# micromouse.net
KiCad netlist of a schematic drawn in EAGLE
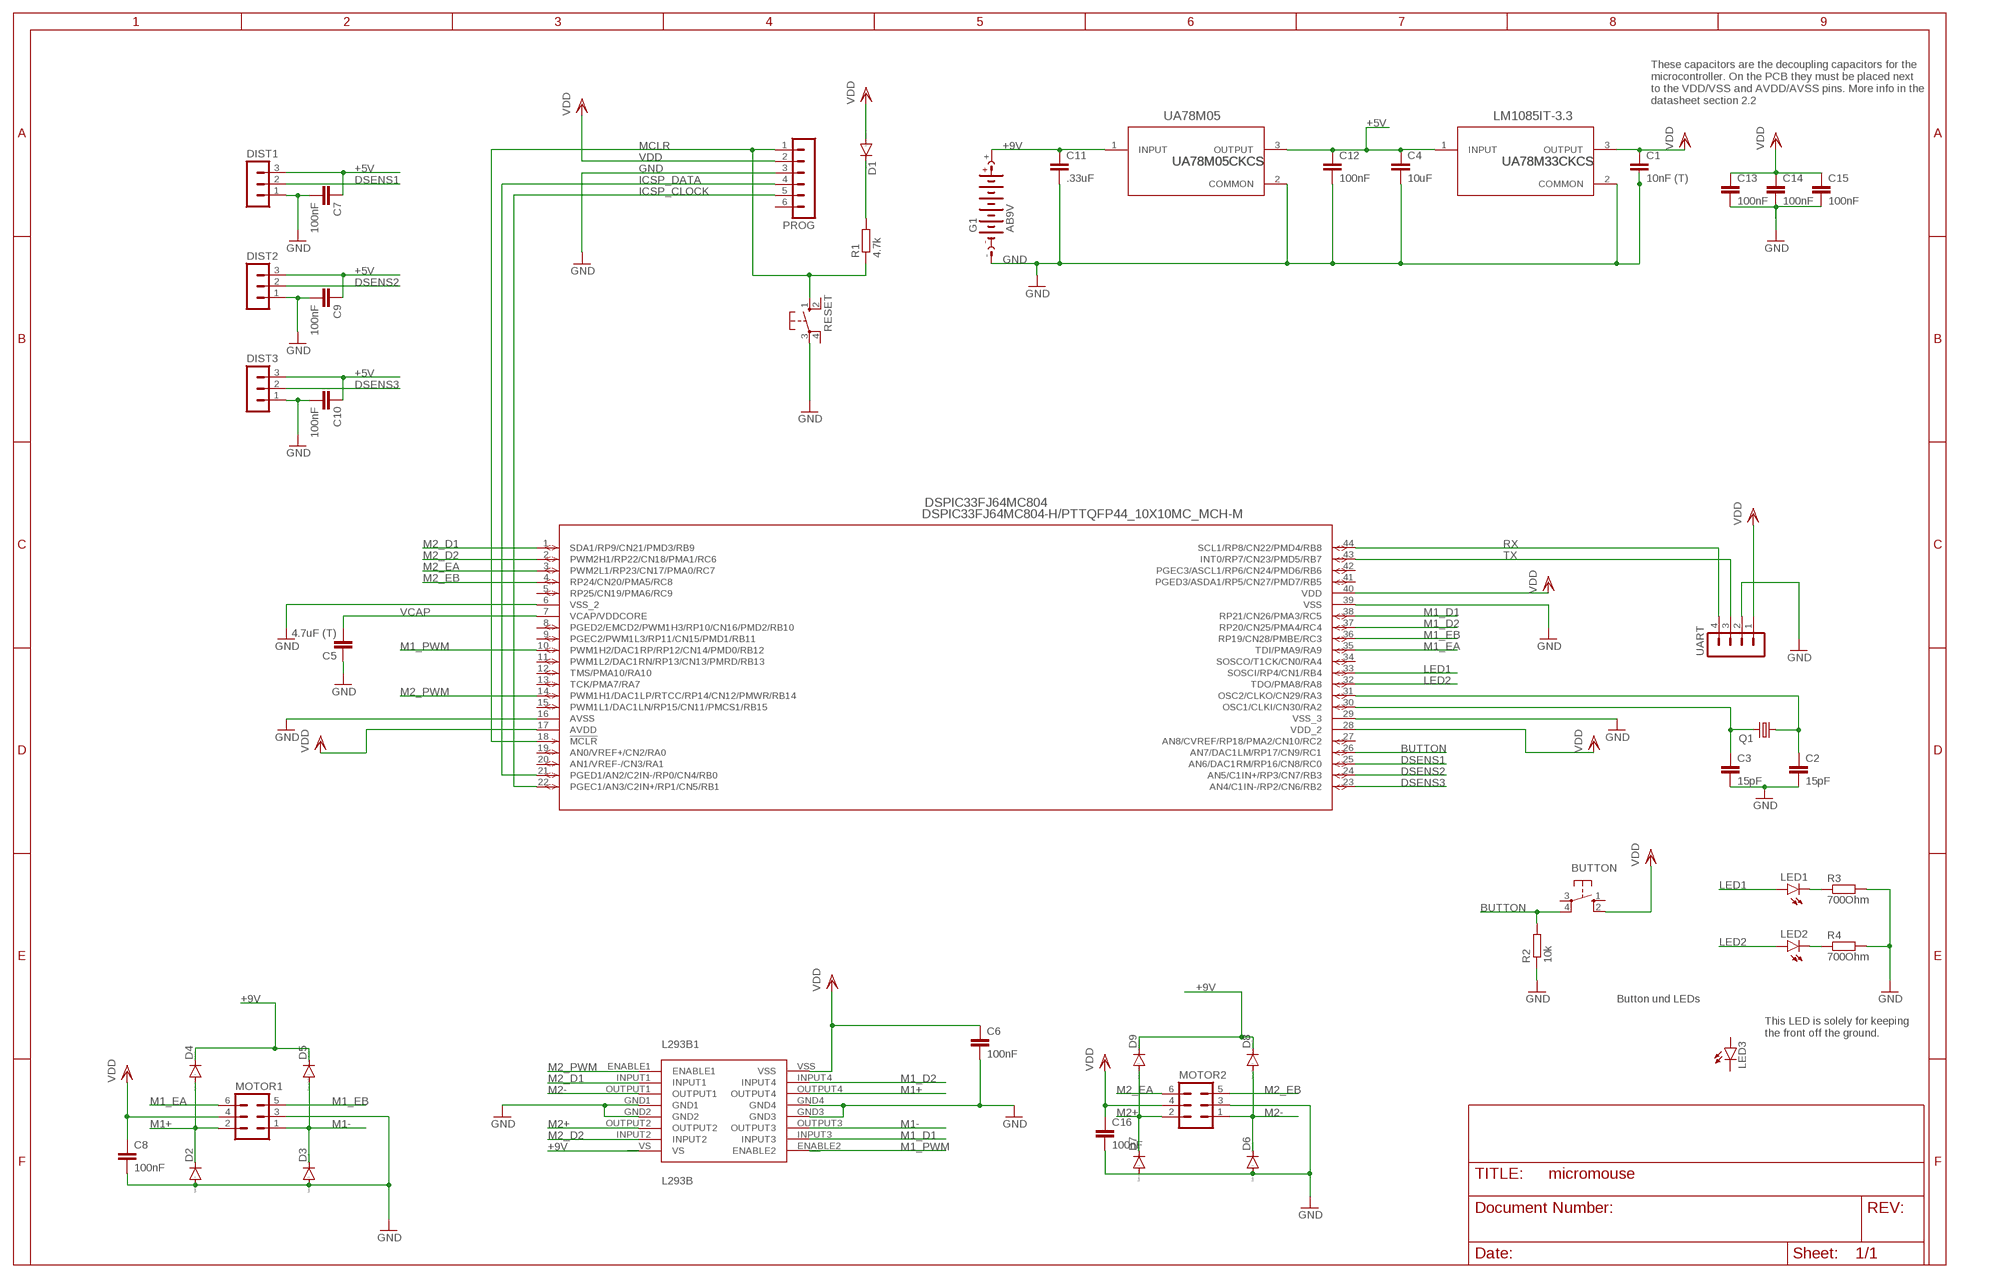
[diagram p0: schematic, sheet 1]

(export (version "E")
  (design (tool "Eeschema 10.0.6"))
  (components
    (comp (ref "BUTTON")
      (value "10-XX")
      (footprint "eagle-import:B3F-10XX")
      (fields (field (name "MPN") "B3F-1000"))
      (libsource (lib "eagle-import") (part "10-XX"))
    )
    (comp (ref "C1")
      (value "10nF (T)")
      (footprint "eagle-import:C0805")
      (libsource (lib "eagle-import") (part "C-EUC0805"))
    )
    (comp (ref "C2")
      (value "15pF")
      (footprint "eagle-import:C0805")
      (libsource (lib "eagle-import") (part "C-EUC0805"))
    )
    (comp (ref "C3")
      (value "15pF")
      (footprint "eagle-import:C0805")
      (libsource (lib "eagle-import") (part "C-EUC0805"))
    )
    (comp (ref "C4")
      (value "10uF")
      (footprint "eagle-import:C0805")
      (libsource (lib "eagle-import") (part "C-EUC0805"))
    )
    (comp (ref "C5")
      (value "4.7uF (T)")
      (footprint "eagle-import:C0805")
      (libsource (lib "eagle-import") (part "C-EUC0805"))
    )
    (comp (ref "C6")
      (value "100nF")
      (footprint "eagle-import:C0805")
      (libsource (lib "eagle-import") (part "C-EUC0805"))
    )
    (comp (ref "C7")
      (value "100nF")
      (footprint "eagle-import:C0805")
      (libsource (lib "eagle-import") (part "C-EUC0805"))
    )
    (comp (ref "C8")
      (value "100nF")
      (footprint "eagle-import:C0805")
      (libsource (lib "eagle-import") (part "C-EUC0805"))
    )
    (comp (ref "C9")
      (value "100nF")
      (footprint "eagle-import:C0805")
      (libsource (lib "eagle-import") (part "C-EUC0805"))
    )
    (comp (ref "C10")
      (value "100nF")
      (footprint "eagle-import:C0805")
      (libsource (lib "eagle-import") (part "C-EUC0805"))
    )
    (comp (ref "C11")
      (value ".33uF")
      (footprint "eagle-import:C0805")
      (libsource (lib "eagle-import") (part "C-EUC0805"))
    )
    (comp (ref "C12")
      (value "100nF")
      (footprint "eagle-import:C0805")
      (libsource (lib "eagle-import") (part "C-EUC0805"))
    )
    (comp (ref "C13")
      (value "100nF")
      (footprint "eagle-import:C0805")
      (libsource (lib "eagle-import") (part "C-EUC0805"))
    )
    (comp (ref "C14")
      (value "100nF")
      (footprint "eagle-import:C0805")
      (libsource (lib "eagle-import") (part "C-EUC0805"))
    )
    (comp (ref "C15")
      (value "100nF")
      (footprint "eagle-import:C0805")
      (libsource (lib "eagle-import") (part "C-EUC0805"))
    )
    (comp (ref "C16")
      (value "100nF")
      (footprint "eagle-import:C0805")
      (libsource (lib "eagle-import") (part "C-EUC0805"))
    )
    (comp (ref "D1")
      (value "DIODE-SOD123")
      (footprint "eagle-import:SOD123")
      (libsource (lib "eagle-import") (part "DIODE-SOD123"))
    )
    (comp (ref "D2")
      (value "DIODE-SOD123")
      (footprint "eagle-import:SOD123")
      (libsource (lib "eagle-import") (part "DIODE-SOD123"))
    )
    (comp (ref "D3")
      (value "DIODE-SOD123")
      (footprint "eagle-import:SOD123")
      (libsource (lib "eagle-import") (part "DIODE-SOD123"))
    )
    (comp (ref "D4")
      (value "DIODE-SOD123")
      (footprint "eagle-import:SOD123")
      (libsource (lib "eagle-import") (part "DIODE-SOD123"))
    )
    (comp (ref "D5")
      (value "DIODE-SOD123")
      (footprint "eagle-import:SOD123")
      (libsource (lib "eagle-import") (part "DIODE-SOD123"))
    )
    (comp (ref "D6")
      (value "DIODE-SOD123")
      (footprint "eagle-import:SOD123")
      (libsource (lib "eagle-import") (part "DIODE-SOD123"))
    )
    (comp (ref "D7")
      (value "DIODE-SOD123")
      (footprint "eagle-import:SOD123")
      (libsource (lib "eagle-import") (part "DIODE-SOD123"))
    )
    (comp (ref "D8")
      (value "DIODE-SOD123")
      (footprint "eagle-import:SOD123")
      (libsource (lib "eagle-import") (part "DIODE-SOD123"))
    )
    (comp (ref "D9")
      (value "DIODE-SOD123")
      (footprint "eagle-import:SOD123")
      (libsource (lib "eagle-import") (part "DIODE-SOD123"))
    )
    (comp (ref "DIST1")
      (value "MA03-1")
      (footprint "eagle-import:MA03-1")
      (libsource (lib "eagle-import") (part "MA03-1"))
    )
    (comp (ref "DIST2")
      (value "MA03-1")
      (footprint "eagle-import:MA03-1")
      (libsource (lib "eagle-import") (part "MA03-1"))
    )
    (comp (ref "DIST3")
      (value "MA03-1")
      (footprint "eagle-import:MA03-1")
      (libsource (lib "eagle-import") (part "MA03-1"))
    )
    (comp (ref "DSPIC33FJ64MC804")
      (value "DSPIC33FJ64MC804-H/PTTQFP44_10X10MC_MCH-M")
      (footprint "eagle-import:TQFP44_10X10MC_MCH-M")
      (fields
        (field (name "MANUFACTURER_PART_NUMBER") "DSPIC33FJ64MC804-H/PT")
        (field (name "COPYRIGHT") "Copyright (C) 2022 Ultra Librarian. All rights reserved.")
      )
      (libsource (lib "eagle-import") (part "DSPIC33FJ64MC804-H/PTTQFP44_10X10MC_MCH-M"))
    )
    (comp (ref "G1")
      (value "AB9V")
      (footprint "eagle-import:AB9V")
      (libsource (lib "eagle-import") (part "AB9V"))
    )
    (comp (ref "L293B1")
      (value "L293B")
      (footprint "eagle-import:L293P-DIP16")
      (libsource (lib "eagle-import") (part "L293B"))
    )
    (comp (ref "LED1")
      (value "LEDCHIP-LED0805")
      (footprint "eagle-import:CHIP-LED0805")
      (libsource (lib "eagle-import") (part "LEDCHIP-LED0805"))
    )
    (comp (ref "LED2")
      (value "LEDCHIP-LED0805")
      (footprint "eagle-import:CHIP-LED0805")
      (libsource (lib "eagle-import") (part "LEDCHIP-LED0805"))
    )
    (comp (ref "LED3")
      (value "LED5MM")
      (footprint "eagle-import:LED5MM")
      (libsource (lib "eagle-import") (part "LED5MM"))
    )
    (comp (ref "LM1085IT-3.3")
      (value "UA78M33CKCS")
      (footprint "eagle-import:KCS0003B")
      (fields
        (field (name "MANUFACTURER_PART_NUMBER") "UA78M05CKCS")
        (field (name "COPYRIGHT") "Copyright (C) 2022 Ultra Librarian. All rights reserved.")
      )
      (libsource (lib "eagle-import") (part "UA78M33CKCS"))
    )
    (comp (ref "MOTOR1")
      (value "MA03-2")
      (footprint "eagle-import:MA03-2")
      (libsource (lib "eagle-import") (part "MA03-2"))
    )
    (comp (ref "MOTOR2")
      (value "MA03-2")
      (footprint "eagle-import:MA03-2")
      (libsource (lib "eagle-import") (part "MA03-2"))
    )
    (comp (ref "PROG")
      (value "MA06-1")
      (footprint "eagle-import:MA06-1")
      (libsource (lib "eagle-import") (part "MA06-1"))
    )
    (comp (ref "Q1")
      (value "CRYSTALHC49S")
      (footprint "eagle-import:HC49_S")
      (libsource (lib "eagle-import") (part "CRYSTALHC49S"))
    )
    (comp (ref "R1")
      (value "4.7k")
      (footprint "eagle-import:R0805")
      (libsource (lib "eagle-import") (part "R-EU_R0805"))
    )
    (comp (ref "R2")
      (value "10k")
      (footprint "eagle-import:R0805")
      (libsource (lib "eagle-import") (part "R-EU_R0805"))
    )
    (comp (ref "R3")
      (value "700Ohm")
      (footprint "eagle-import:R0805")
      (libsource (lib "eagle-import") (part "R-EU_R0805"))
    )
    (comp (ref "R4")
      (value "700Ohm")
      (footprint "eagle-import:R0805")
      (libsource (lib "eagle-import") (part "R-EU_R0805"))
    )
    (comp (ref "RESET")
      (value "10-XX")
      (footprint "eagle-import:B3F-10XX")
      (fields (field (name "MPN") "B3F-1000"))
      (libsource (lib "eagle-import") (part "10-XX"))
    )
    (comp (ref "UA78M05")
      (value "UA78M05CKCS")
      (footprint "eagle-import:KCS0003B")
      (fields (field (name "COPYRIGHT") "Copyright (C) 2022 Ultra Librarian. All rights reserved."))
      (libsource (lib "eagle-import") (part "UA78M05CKCS"))
    )
    (comp (ref "UART")
      (value "MA04-1")
      (footprint "eagle-import:MA04-1")
      (libsource (lib "eagle-import") (part "MA04-1"))
    )
  )
  (nets
    (net (code "1") (name "/+5V") (class "Default")
      (node (ref "C10") (pin "1") (pinfunction "1_1") (pintype "passive"))
      (node (ref "C12") (pin "1") (pinfunction "1_1") (pintype "passive"))
      (node (ref "C4") (pin "1") (pinfunction "1_1") (pintype "passive"))
      (node (ref "C7") (pin "1") (pinfunction "1_1") (pintype "passive"))
      (node (ref "C9") (pin "1") (pinfunction "1_1") (pintype "passive"))
      (node (ref "DIST1") (pin "3") (pinfunction "3_3") (pintype "passive"))
      (node (ref "DIST2") (pin "3") (pinfunction "3_3") (pintype "passive"))
      (node (ref "DIST3") (pin "3") (pinfunction "3_3") (pintype "passive"))
      (node (ref "LM1085IT-3.3") (pin "1") (pinfunction "INPUT_1") (pintype "power_in"))
      (node (ref "UA78M05") (pin "3") (pinfunction "OUTPUT_3") (pintype "power_in"))
    )
    (net (code "2") (name "/+9V") (class "Default")
      (node (ref "C11") (pin "1") (pinfunction "1_1") (pintype "passive"))
      (node (ref "D4") (pin "C") (pinfunction "C_C") (pintype "passive"))
      (node (ref "D5") (pin "C") (pinfunction "C_C") (pintype "passive"))
      (node (ref "D8") (pin "C") (pinfunction "C_C") (pintype "passive"))
      (node (ref "D9") (pin "C") (pinfunction "C_C") (pintype "passive"))
      (node (ref "G1") (pin "+") (pinfunction "+_+") (pintype "passive"))
      (node (ref "L293B1") (pin "VS") (pinfunction "VS_VS") (pintype "bidirectional"))
      (node (ref "UA78M05") (pin "1") (pinfunction "INPUT_1") (pintype "power_in"))
    )
    (net (code "3") (name "/BUTTON") (class "Default")
      (node (ref "BUTTON") (pin "4") (pinfunction "P1_4") (pintype "passive"))
      (node (ref "DSPIC33FJ64MC804") (pin "26") (pinfunction "AN7/DAC1LM/RP17/CN9/RC1_26") (pintype "bidirectional"))
      (node (ref "R2") (pin "2") (pinfunction "2_2") (pintype "passive"))
    )
    (net (code "4") (name "/DSENS1") (class "Default")
      (node (ref "DIST1") (pin "2") (pinfunction "2_2") (pintype "passive"))
      (node (ref "DSPIC33FJ64MC804") (pin "25") (pinfunction "AN6/DAC1RM/RP16/CN8/RC0_25") (pintype "bidirectional"))
    )
    (net (code "5") (name "/DSENS2") (class "Default")
      (node (ref "DIST2") (pin "2") (pinfunction "2_2") (pintype "passive"))
      (node (ref "DSPIC33FJ64MC804") (pin "24") (pinfunction "AN5/C1IN+/RP3/CN7/RB3_24") (pintype "bidirectional"))
    )
    (net (code "6") (name "/DSENS3") (class "Default")
      (node (ref "DIST3") (pin "2") (pinfunction "2_2") (pintype "passive"))
      (node (ref "DSPIC33FJ64MC804") (pin "23") (pinfunction "AN4/C1IN-/RP2/CN6/RB2_23") (pintype "bidirectional"))
    )
    (net (code "7") (name "/ICSP_CLOCK") (class "Default")
      (node (ref "DSPIC33FJ64MC804") (pin "22") (pinfunction "PGEC1/AN3/C2IN+/RP1/CN5/RB1_22") (pintype "bidirectional"))
      (node (ref "PROG") (pin "5") (pinfunction "5_5") (pintype "passive"))
    )
    (net (code "8") (name "/ICSP_DATA") (class "Default")
      (node (ref "DSPIC33FJ64MC804") (pin "21") (pinfunction "PGED1/AN2/C2IN-/RP0/CN4/RB0_21") (pintype "bidirectional"))
      (node (ref "PROG") (pin "4") (pinfunction "4_4") (pintype "passive"))
    )
    (net (code "9") (name "/LED1") (class "Default")
      (node (ref "DSPIC33FJ64MC804") (pin "33") (pinfunction "SOSCI/RP4/CN1/RB4_33") (pintype "bidirectional"))
      (node (ref "LED1") (pin "A") (pinfunction "A_A") (pintype "passive"))
    )
    (net (code "10") (name "/LED2") (class "Default")
      (node (ref "DSPIC33FJ64MC804") (pin "32") (pinfunction "TDO/PMA8/RA8_32") (pintype "bidirectional"))
      (node (ref "LED2") (pin "A") (pinfunction "A_A") (pintype "passive"))
    )
    (net (code "11") (name "/M1+") (class "Default")
      (node (ref "D2") (pin "C") (pinfunction "C_C") (pintype "passive"))
      (node (ref "D4") (pin "A") (pinfunction "A_A") (pintype "passive"))
      (node (ref "L293B1") (pin "OUTPUT4") (pinfunction "OUTPUT4_OUTPUT4") (pintype "bidirectional"))
      (node (ref "MOTOR1") (pin "2") (pinfunction "2_2") (pintype "passive"))
    )
    (net (code "12") (name "/M1-") (class "Default")
      (node (ref "D3") (pin "C") (pinfunction "C_C") (pintype "passive"))
      (node (ref "D5") (pin "A") (pinfunction "A_A") (pintype "passive"))
      (node (ref "L293B1") (pin "OUTPUT3") (pinfunction "OUTPUT3_OUTPUT3") (pintype "bidirectional"))
      (node (ref "MOTOR1") (pin "1") (pinfunction "1_1") (pintype "passive"))
    )
    (net (code "13") (name "/M1_D1") (class "Default")
      (node (ref "DSPIC33FJ64MC804") (pin "38") (pinfunction "RP21/CN26/PMA3/RC5_38") (pintype "bidirectional"))
      (node (ref "L293B1") (pin "INPUT3") (pinfunction "INPUT3_INPUT3") (pintype "bidirectional"))
    )
    (net (code "14") (name "/M1_D2") (class "Default")
      (node (ref "DSPIC33FJ64MC804") (pin "37") (pinfunction "RP20/CN25/PMA4/RC4_37") (pintype "bidirectional"))
      (node (ref "L293B1") (pin "INPUT4") (pinfunction "INPUT4_INPUT4") (pintype "bidirectional"))
    )
    (net (code "15") (name "/M1_EA") (class "Default")
      (node (ref "DSPIC33FJ64MC804") (pin "35") (pinfunction "TDI/PMA9/RA9_35") (pintype "bidirectional"))
      (node (ref "MOTOR1") (pin "6") (pinfunction "6_6") (pintype "passive"))
    )
    (net (code "16") (name "/M1_EB") (class "Default")
      (node (ref "DSPIC33FJ64MC804") (pin "36") (pinfunction "RP19/CN28/PMBE/RC3_36") (pintype "bidirectional"))
      (node (ref "MOTOR1") (pin "5") (pinfunction "5_5") (pintype "passive"))
    )
    (net (code "17") (name "/M1_PWM") (class "Default")
      (node (ref "DSPIC33FJ64MC804") (pin "10") (pinfunction "PWM1H2/DAC1RP/RP12/CN14/PMD0/RB12_10") (pintype "bidirectional"))
      (node (ref "L293B1") (pin "ENABLE2") (pinfunction "ENABLE2_ENABLE2") (pintype "bidirectional"))
    )
    (net (code "18") (name "/M2+") (class "Default")
      (node (ref "D7") (pin "C") (pinfunction "C_C") (pintype "passive"))
      (node (ref "D9") (pin "A") (pinfunction "A_A") (pintype "passive"))
      (node (ref "L293B1") (pin "OUTPUT2") (pinfunction "OUTPUT2_OUTPUT2") (pintype "bidirectional"))
      (node (ref "MOTOR2") (pin "2") (pinfunction "2_2") (pintype "passive"))
    )
    (net (code "19") (name "/M2-") (class "Default")
      (node (ref "D6") (pin "C") (pinfunction "C_C") (pintype "passive"))
      (node (ref "D8") (pin "A") (pinfunction "A_A") (pintype "passive"))
      (node (ref "L293B1") (pin "OUTPUT1") (pinfunction "OUTPUT1_OUTPUT1") (pintype "bidirectional"))
      (node (ref "MOTOR2") (pin "1") (pinfunction "1_1") (pintype "passive"))
    )
    (net (code "20") (name "/M2_D1") (class "Default")
      (node (ref "DSPIC33FJ64MC804") (pin "1") (pinfunction "SDA1/RP9/CN21/PMD3/RB9_1") (pintype "bidirectional"))
      (node (ref "L293B1") (pin "INPUT1") (pinfunction "INPUT1_INPUT1") (pintype "bidirectional"))
    )
    (net (code "21") (name "/M2_D2") (class "Default")
      (node (ref "DSPIC33FJ64MC804") (pin "2") (pinfunction "PWM2H1/RP22/CN18/PMA1/RC6_2") (pintype "bidirectional"))
      (node (ref "L293B1") (pin "INPUT2") (pinfunction "INPUT2_INPUT2") (pintype "bidirectional"))
    )
    (net (code "22") (name "/M2_EA") (class "Default")
      (node (ref "DSPIC33FJ64MC804") (pin "3") (pinfunction "PWM2L1/RP23/CN17/PMA0/RC7_3") (pintype "bidirectional"))
      (node (ref "MOTOR2") (pin "6") (pinfunction "6_6") (pintype "passive"))
    )
    (net (code "23") (name "/M2_EB") (class "Default")
      (node (ref "DSPIC33FJ64MC804") (pin "4") (pinfunction "RP24/CN20/PMA5/RC8_4") (pintype "bidirectional"))
      (node (ref "MOTOR2") (pin "5") (pinfunction "5_5") (pintype "passive"))
    )
    (net (code "24") (name "/M2_PWM") (class "Default")
      (node (ref "DSPIC33FJ64MC804") (pin "14") (pinfunction "PWM1H1/DAC1LP/RTCC/RP14/CN12/PMWR/RB14_14") (pintype "bidirectional"))
      (node (ref "L293B1") (pin "ENABLE1") (pinfunction "ENABLE1_ENABLE1") (pintype "bidirectional"))
    )
    (net (code "25") (name "/MCLR") (class "Default")
      (node (ref "DSPIC33FJ64MC804") (pin "18") (pinfunction "~{MCLR}_18") (pintype "input"))
      (node (ref "PROG") (pin "1") (pinfunction "1_1") (pintype "passive"))
      (node (ref "R1") (pin "1") (pinfunction "1_1") (pintype "passive"))
      (node (ref "RESET") (pin "1") (pinfunction "S_1") (pintype "passive"))
    )
    (net (code "26") (name "/RX") (class "Default")
      (node (ref "DSPIC33FJ64MC804") (pin "44") (pinfunction "SCL1/RP8/CN22/PMD4/RB8_44") (pintype "bidirectional"))
      (node (ref "UART") (pin "4") (pinfunction "4_4") (pintype "passive"))
    )
    (net (code "27") (name "/TX") (class "Default")
      (node (ref "DSPIC33FJ64MC804") (pin "43") (pinfunction "INT0/RP7/CN23/PMD5/RB7_43") (pintype "bidirectional"))
      (node (ref "UART") (pin "3") (pinfunction "3_3") (pintype "passive"))
    )
    (net (code "28") (name "/VCAP") (class "Default")
      (node (ref "C5") (pin "2") (pinfunction "2_2") (pintype "passive"))
      (node (ref "DSPIC33FJ64MC804") (pin "7") (pinfunction "VCAP/VDDCORE_7") (pintype "power_in"))
    )
    (net (code "29") (name "GND") (class "Default")
      (node (ref "C1") (pin "2") (pinfunction "2_2") (pintype "passive"))
      (node (ref "C10") (pin "2") (pinfunction "2_2") (pintype "passive"))
      (node (ref "C11") (pin "2") (pinfunction "2_2") (pintype "passive"))
      (node (ref "C12") (pin "2") (pinfunction "2_2") (pintype "passive"))
      (node (ref "C13") (pin "2") (pinfunction "2_2") (pintype "passive"))
      (node (ref "C14") (pin "2") (pinfunction "2_2") (pintype "passive"))
      (node (ref "C15") (pin "2") (pinfunction "2_2") (pintype "passive"))
      (node (ref "C16") (pin "2") (pinfunction "2_2") (pintype "passive"))
      (node (ref "C2") (pin "2") (pinfunction "2_2") (pintype "passive"))
      (node (ref "C3") (pin "2") (pinfunction "2_2") (pintype "passive"))
      (node (ref "C4") (pin "2") (pinfunction "2_2") (pintype "passive"))
      (node (ref "C5") (pin "1") (pinfunction "1_1") (pintype "passive"))
      (node (ref "C6") (pin "2") (pinfunction "2_2") (pintype "passive"))
      (node (ref "C7") (pin "2") (pinfunction "2_2") (pintype "passive"))
      (node (ref "C8") (pin "2") (pinfunction "2_2") (pintype "passive"))
      (node (ref "C9") (pin "2") (pinfunction "2_2") (pintype "passive"))
      (node (ref "D2") (pin "A") (pinfunction "A_A") (pintype "passive"))
      (node (ref "D3") (pin "A") (pinfunction "A_A") (pintype "passive"))
      (node (ref "D6") (pin "A") (pinfunction "A_A") (pintype "passive"))
      (node (ref "D7") (pin "A") (pinfunction "A_A") (pintype "passive"))
      (node (ref "DIST1") (pin "1") (pinfunction "1_1") (pintype "passive"))
      (node (ref "DIST2") (pin "1") (pinfunction "1_1") (pintype "passive"))
      (node (ref "DIST3") (pin "1") (pinfunction "1_1") (pintype "passive"))
      (node (ref "DSPIC33FJ64MC804") (pin "16") (pinfunction "AVSS_16") (pintype "power_in"))
      (node (ref "DSPIC33FJ64MC804") (pin "29") (pinfunction "VSS_3_29") (pintype "power_in"))
      (node (ref "DSPIC33FJ64MC804") (pin "39") (pinfunction "VSS_39") (pintype "power_in"))
      (node (ref "DSPIC33FJ64MC804") (pin "6") (pinfunction "VSS_2_6") (pintype "power_in"))
      (node (ref "G1") (pin "-") (pinfunction "-_-") (pintype "passive"))
      (node (ref "L293B1") (pin "GND1") (pinfunction "GND1_GND1") (pintype "bidirectional"))
      (node (ref "L293B1") (pin "GND2") (pinfunction "GND2_GND2") (pintype "bidirectional"))
      (node (ref "L293B1") (pin "GND3") (pinfunction "GND3_GND3") (pintype "bidirectional"))
      (node (ref "L293B1") (pin "GND4") (pinfunction "GND4_GND4") (pintype "bidirectional"))
      (node (ref "LM1085IT-3.3") (pin "2") (pinfunction "COMMON_2") (pintype "power_in"))
      (node (ref "MOTOR1") (pin "3") (pinfunction "3_3") (pintype "passive"))
      (node (ref "MOTOR2") (pin "3") (pinfunction "3_3") (pintype "passive"))
      (node (ref "PROG") (pin "3") (pinfunction "3_3") (pintype "passive"))
      (node (ref "R2") (pin "1") (pinfunction "1_1") (pintype "passive"))
      (node (ref "R3") (pin "2") (pinfunction "2_2") (pintype "passive"))
      (node (ref "R4") (pin "2") (pinfunction "2_2") (pintype "passive"))
      (node (ref "RESET") (pin "3") (pinfunction "P_3") (pintype "passive"))
      (node (ref "UA78M05") (pin "2") (pinfunction "COMMON_2") (pintype "power_in"))
      (node (ref "UART") (pin "2") (pinfunction "2_2") (pintype "passive"))
    )
    (net (code "30") (name "Net-(D1-PadC)") (class "Default")
      (node (ref "D1") (pin "C") (pinfunction "C_C") (pintype "passive"))
      (node (ref "R1") (pin "2") (pinfunction "2_2") (pintype "passive"))
    )
    (net (code "31") (name "Net-(DSPIC33FJ64MC804-OSC1{slash}CLKI{slash}CN30{slash}RA2)") (class "Default")
      (node (ref "C3") (pin "1") (pinfunction "1_1") (pintype "passive"))
      (node (ref "DSPIC33FJ64MC804") (pin "30") (pinfunction "OSC1/CLKI/CN30/RA2_30") (pintype "bidirectional"))
      (node (ref "Q1") (pin "2") (pinfunction "2_2") (pintype "passive"))
    )
    (net (code "32") (name "Net-(DSPIC33FJ64MC804-OSC2{slash}CLKO{slash}CN29{slash}RA3)") (class "Default")
      (node (ref "C2") (pin "1") (pinfunction "1_1") (pintype "passive"))
      (node (ref "DSPIC33FJ64MC804") (pin "31") (pinfunction "OSC2/CLKO/CN29/RA3_31") (pintype "bidirectional"))
      (node (ref "Q1") (pin "1") (pinfunction "1_1") (pintype "passive"))
    )
    (net (code "33") (name "Net-(LED1-PadC)") (class "Default")
      (node (ref "LED1") (pin "C") (pinfunction "C_C") (pintype "passive"))
      (node (ref "R3") (pin "1") (pinfunction "1_1") (pintype "passive"))
    )
    (net (code "34") (name "Net-(LED2-PadC)") (class "Default")
      (node (ref "LED2") (pin "C") (pinfunction "C_C") (pintype "passive"))
      (node (ref "R4") (pin "1") (pinfunction "1_1") (pintype "passive"))
    )
    (net (code "35") (name "VDD") (class "Default")
      (node (ref "BUTTON") (pin "2") (pinfunction "S1_2") (pintype "passive"))
      (node (ref "C1") (pin "1") (pinfunction "1_1") (pintype "passive"))
      (node (ref "C13") (pin "1") (pinfunction "1_1") (pintype "passive"))
      (node (ref "C14") (pin "1") (pinfunction "1_1") (pintype "passive"))
      (node (ref "C15") (pin "1") (pinfunction "1_1") (pintype "passive"))
      (node (ref "C16") (pin "1") (pinfunction "1_1") (pintype "passive"))
      (node (ref "C6") (pin "1") (pinfunction "1_1") (pintype "passive"))
      (node (ref "C8") (pin "1") (pinfunction "1_1") (pintype "passive"))
      (node (ref "D1") (pin "A") (pinfunction "A_A") (pintype "passive"))
      (node (ref "DSPIC33FJ64MC804") (pin "17") (pinfunction "AVDD_17") (pintype "power_in"))
      (node (ref "DSPIC33FJ64MC804") (pin "28") (pinfunction "VDD_2_28") (pintype "power_in"))
      (node (ref "DSPIC33FJ64MC804") (pin "40") (pinfunction "VDD_40") (pintype "power_in"))
      (node (ref "L293B1") (pin "VSS") (pinfunction "VSS_VSS") (pintype "bidirectional"))
      (node (ref "LM1085IT-3.3") (pin "3") (pinfunction "OUTPUT_3") (pintype "power_in"))
      (node (ref "MOTOR1") (pin "4") (pinfunction "4_4") (pintype "passive"))
      (node (ref "MOTOR2") (pin "4") (pinfunction "4_4") (pintype "passive"))
      (node (ref "PROG") (pin "2") (pinfunction "2_2") (pintype "passive"))
      (node (ref "UART") (pin "1") (pinfunction "1_1") (pintype "passive"))
    )
    (net (code "36") (name "unconnected-(BUTTON-P-Pad3)") (class "Default")
      (node (ref "BUTTON") (pin "3") (pinfunction "P_3") (pintype "passive"))
    )
    (net (code "37") (name "unconnected-(BUTTON-S-Pad1)") (class "Default")
      (node (ref "BUTTON") (pin "1") (pinfunction "S_1") (pintype "passive"))
    )
    (net (code "38") (name "unconnected-(DSPIC33FJ64MC804-AN0{slash}VREF+{slash}CN2{slash}RA0-Pad19)") (class "Default")
      (node (ref "DSPIC33FJ64MC804") (pin "19") (pinfunction "AN0/VREF+/CN2/RA0_19") (pintype "bidirectional"))
    )
    (net (code "39") (name "unconnected-(DSPIC33FJ64MC804-AN1{slash}VREF-{slash}CN3{slash}RA1-Pad20)") (class "Default")
      (node (ref "DSPIC33FJ64MC804") (pin "20") (pinfunction "AN1/VREF-/CN3/RA1_20") (pintype "bidirectional"))
    )
    (net (code "40") (name "unconnected-(DSPIC33FJ64MC804-AN8{slash}CVREF{slash}RP18{slash}PMA2{slash}CN10{slash}RC2-Pad27)") (class "Default")
      (node (ref "DSPIC33FJ64MC804") (pin "27") (pinfunction "AN8/CVREF/RP18/PMA2/CN10/RC2_27") (pintype "bidirectional"))
    )
    (net (code "41") (name "unconnected-(DSPIC33FJ64MC804-PGEC2{slash}PWM1L3{slash}RP11{slash}CN15{slash}PMD1{slash}RB11-Pad9)") (class "Default")
      (node (ref "DSPIC33FJ64MC804") (pin "9") (pinfunction "PGEC2/PWM1L3/RP11/CN15/PMD1/RB11_9") (pintype "bidirectional"))
    )
    (net (code "42") (name "unconnected-(DSPIC33FJ64MC804-PGEC3{slash}ASCL1{slash}RP6{slash}CN24{slash}PMD6{slash}RB6-Pad42)") (class "Default")
      (node (ref "DSPIC33FJ64MC804") (pin "42") (pinfunction "PGEC3/ASCL1/RP6/CN24/PMD6/RB6_42") (pintype "bidirectional"))
    )
    (net (code "43") (name "unconnected-(DSPIC33FJ64MC804-PGED2{slash}EMCD2{slash}PWM1H3{slash}RP10{slash}CN16{slash}PMD2{slash}RB10-Pad8)") (class "Default")
      (node (ref "DSPIC33FJ64MC804") (pin "8") (pinfunction "PGED2/EMCD2/PWM1H3/RP10/CN16/PMD2/RB10_8") (pintype "bidirectional"))
    )
    (net (code "44") (name "unconnected-(DSPIC33FJ64MC804-PGED3{slash}ASDA1{slash}RP5{slash}CN27{slash}PMD7{slash}RB5-Pad41)") (class "Default")
      (node (ref "DSPIC33FJ64MC804") (pin "41") (pinfunction "PGED3/ASDA1/RP5/CN27/PMD7/RB5_41") (pintype "bidirectional"))
    )
    (net (code "45") (name "unconnected-(DSPIC33FJ64MC804-PWM1L1{slash}DAC1LN{slash}RP15{slash}CN11{slash}PMCS1{slash}RB15-Pad15)") (class "Default")
      (node (ref "DSPIC33FJ64MC804") (pin "15") (pinfunction "PWM1L1/DAC1LN/RP15/CN11/PMCS1/RB15_15") (pintype "bidirectional"))
    )
    (net (code "46") (name "unconnected-(DSPIC33FJ64MC804-PWM1L2{slash}DAC1RN{slash}RP13{slash}CN13{slash}PMRD{slash}RB13-Pad11)") (class "Default")
      (node (ref "DSPIC33FJ64MC804") (pin "11") (pinfunction "PWM1L2/DAC1RN/RP13/CN13/PMRD/RB13_11") (pintype "bidirectional"))
    )
    (net (code "47") (name "unconnected-(DSPIC33FJ64MC804-RP25{slash}CN19{slash}PMA6{slash}RC9-Pad5)") (class "Default")
      (node (ref "DSPIC33FJ64MC804") (pin "5") (pinfunction "RP25/CN19/PMA6/RC9_5") (pintype "bidirectional"))
    )
    (net (code "48") (name "unconnected-(DSPIC33FJ64MC804-SOSCO{slash}T1CK{slash}CN0{slash}RA4-Pad34)") (class "Default")
      (node (ref "DSPIC33FJ64MC804") (pin "34") (pinfunction "SOSCO/T1CK/CN0/RA4_34") (pintype "bidirectional"))
    )
    (net (code "49") (name "unconnected-(DSPIC33FJ64MC804-TCK{slash}PMA7{slash}RA7-Pad13)") (class "Default")
      (node (ref "DSPIC33FJ64MC804") (pin "13") (pinfunction "TCK/PMA7/RA7_13") (pintype "bidirectional"))
    )
    (net (code "50") (name "unconnected-(DSPIC33FJ64MC804-TMS{slash}PMA10{slash}RA10-Pad12)") (class "Default")
      (node (ref "DSPIC33FJ64MC804") (pin "12") (pinfunction "TMS/PMA10/RA10_12") (pintype "bidirectional"))
    )
    (net (code "51") (name "unconnected-(LED3-C-PadK)") (class "Default")
      (node (ref "LED3") (pin "K") (pinfunction "C_K") (pintype "passive"))
    )
    (net (code "52") (name "unconnected-(LED3-PadA)") (class "Default")
      (node (ref "LED3") (pin "A") (pinfunction "A_A") (pintype "passive"))
    )
    (net (code "53") (name "unconnected-(PROG-Pad6)") (class "Default")
      (node (ref "PROG") (pin "6") (pinfunction "6_6") (pintype "passive"))
    )
    (net (code "54") (name "unconnected-(RESET-P1-Pad4)") (class "Default")
      (node (ref "RESET") (pin "4") (pinfunction "P1_4") (pintype "passive"))
    )
    (net (code "55") (name "unconnected-(RESET-S1-Pad2)") (class "Default")
      (node (ref "RESET") (pin "2") (pinfunction "S1_2") (pintype "passive"))
    )
  )
)
